# zx80_SD_12_smd_build002-001.net
KiCad netlist of a schematic drawn in EAGLE
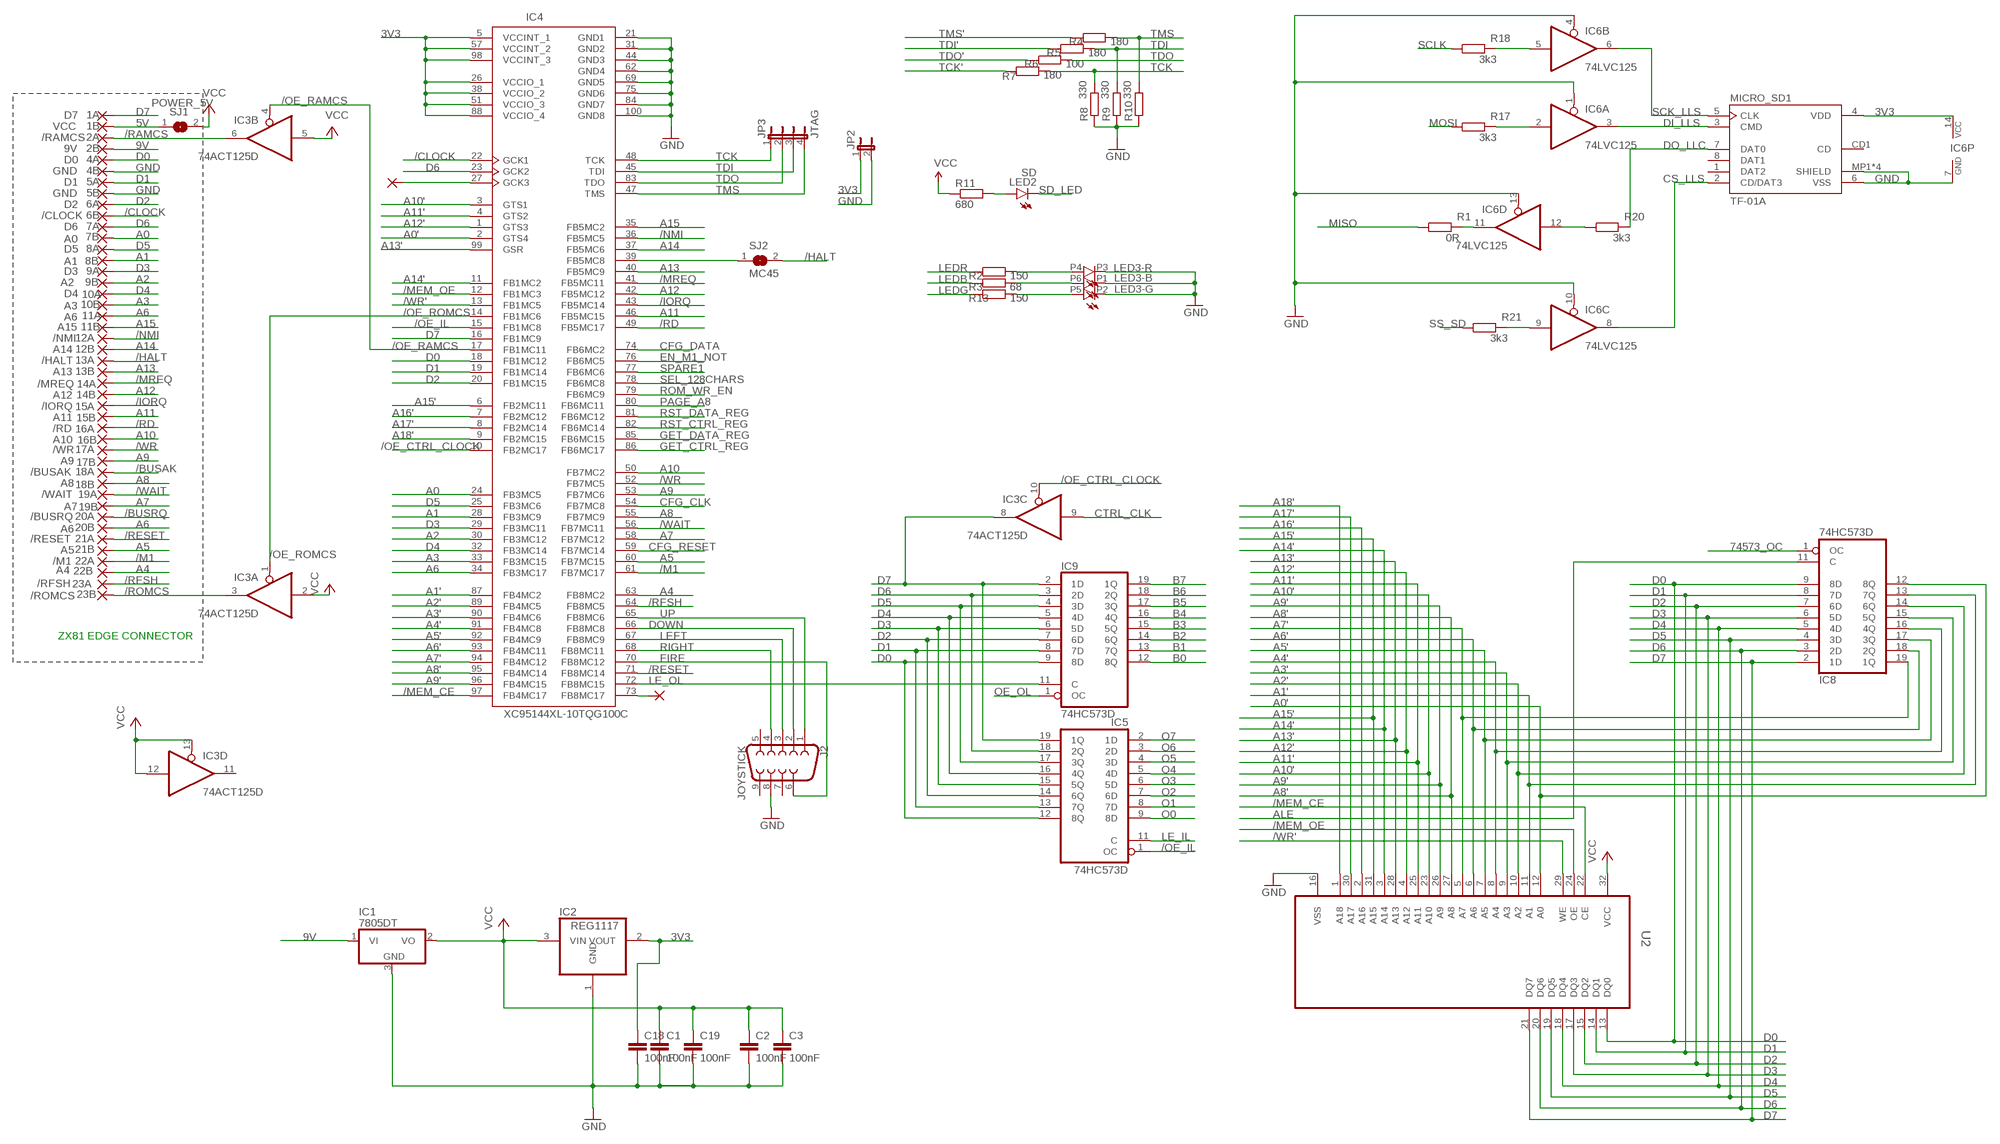
[diagram p0: schematic, sheet 1]
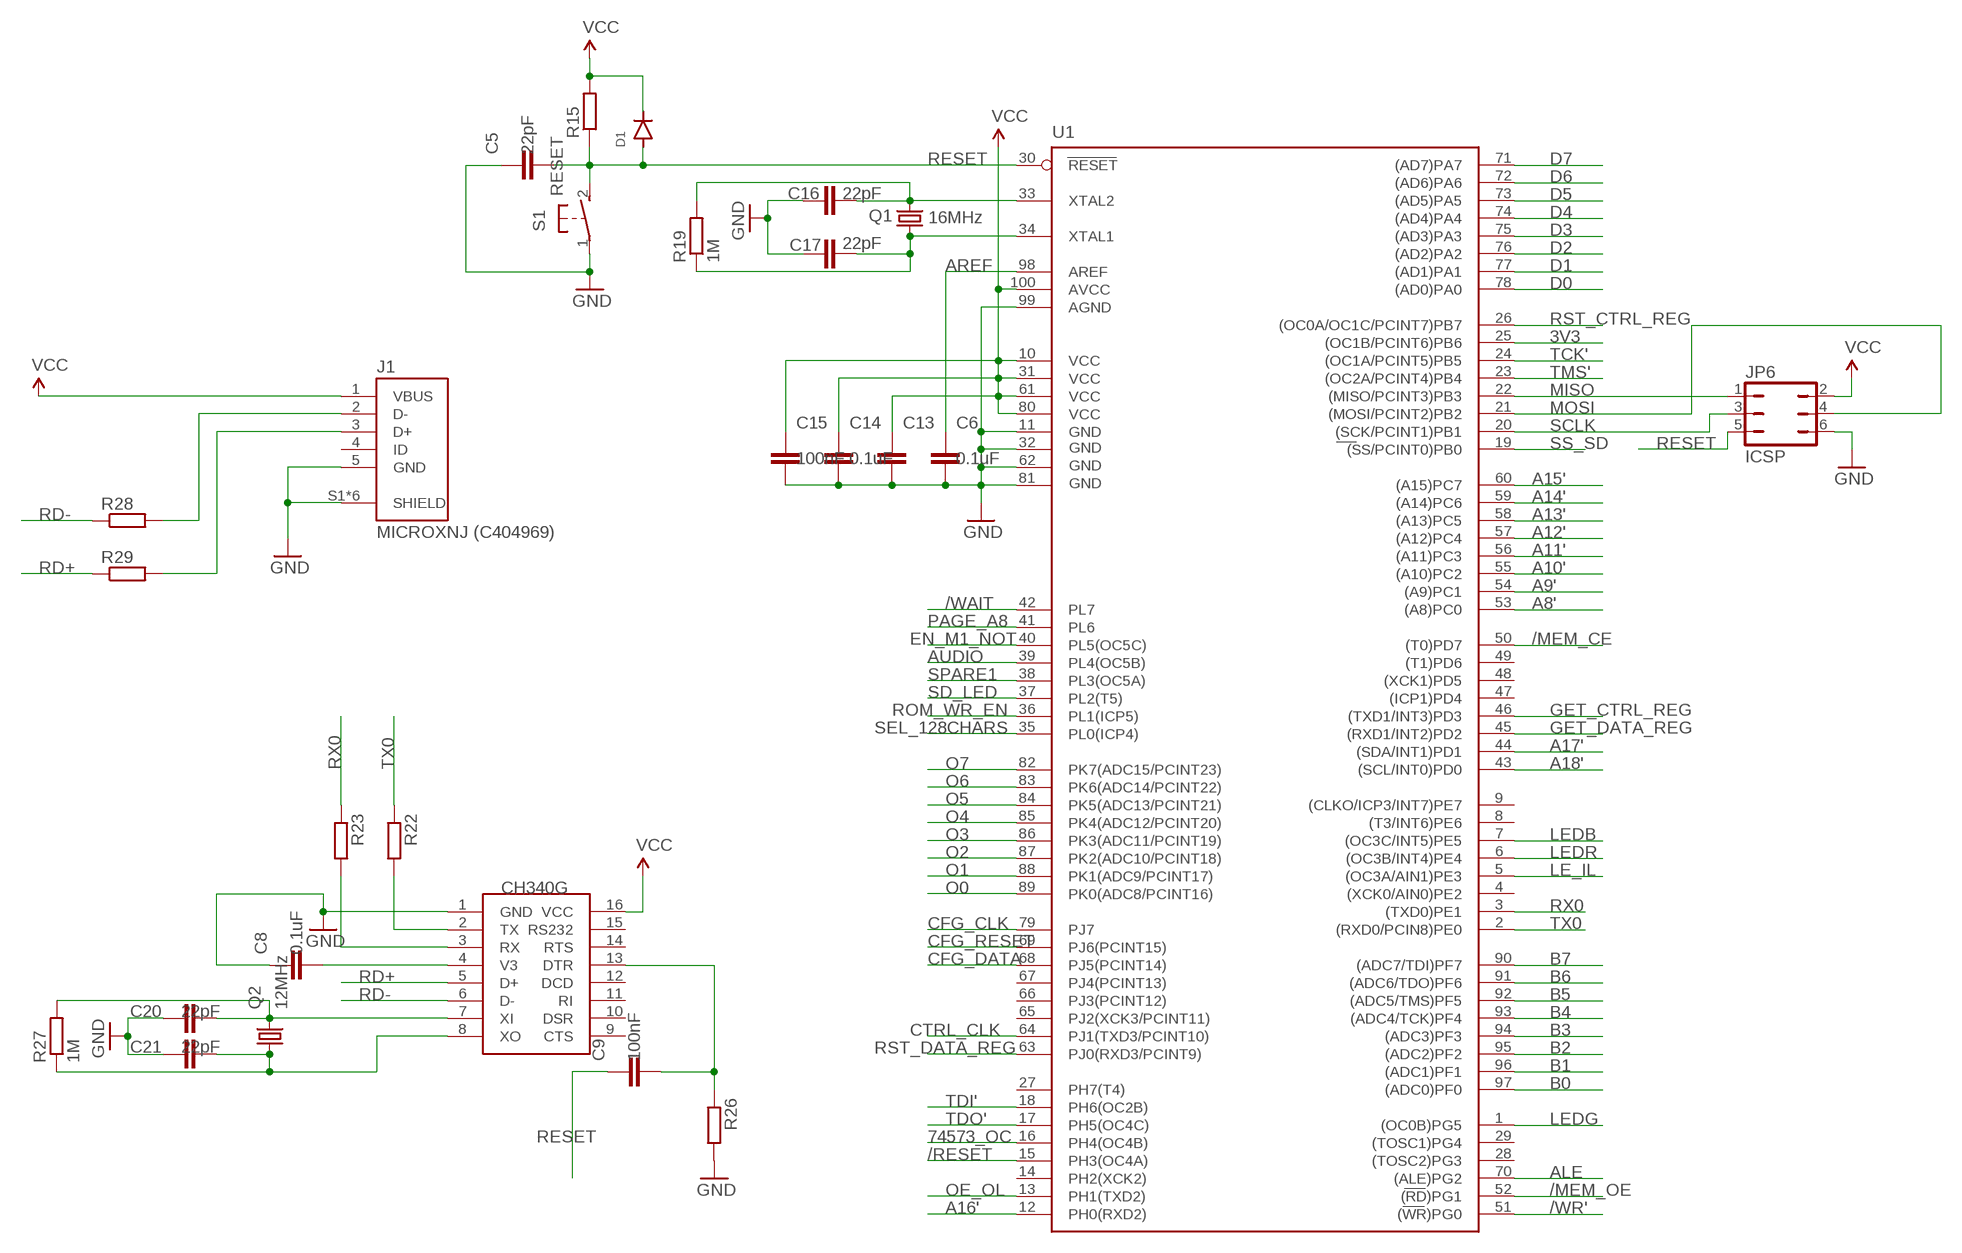
[diagram p1: schematic, sheet 2]

(export (version "E")
  (design (tool "Eeschema 10.0.6"))
  (components
    (comp (ref "C5")
      (value "22pF")
      (footprint "eagle-import:C0603")
      (libsource (lib "eagle-import") (part "C-EUC0603"))
    )
    (comp (ref "C6")
      (value "0.1uF")
      (footprint "eagle-import:C0603")
      (libsource (lib "eagle-import") (part "C-EUC0603"))
    )
    (comp (ref "C8")
      (value "0.1uF")
      (footprint "eagle-import:C0603")
      (libsource (lib "eagle-import") (part "C-EUC0603"))
    )
    (comp (ref "C9")
      (value "100nF")
      (footprint "eagle-import:C0603")
      (libsource (lib "eagle-import") (part "C-EUC0603"))
    )
    (comp (ref "C13")
      (value "0.1uF")
      (footprint "eagle-import:C0603")
      (libsource (lib "eagle-import") (part "C-EUC0603"))
    )
    (comp (ref "C14")
      (value "0.1uF")
      (footprint "eagle-import:C0603")
      (libsource (lib "eagle-import") (part "C-EUC0603"))
    )
    (comp (ref "C15")
      (value "100nF")
      (footprint "eagle-import:C0603")
      (libsource (lib "eagle-import") (part "C-EUC0603"))
    )
    (comp (ref "C16")
      (value "22pF")
      (footprint "eagle-import:C0603")
      (libsource (lib "eagle-import") (part "C-EUC0603"))
    )
    (comp (ref "C17")
      (value "22pF")
      (footprint "eagle-import:C0603")
      (libsource (lib "eagle-import") (part "C-EUC0603"))
    )
    (comp (ref "C20")
      (value "22pF")
      (footprint "eagle-import:C0603")
      (libsource (lib "eagle-import") (part "C-EUC0603"))
    )
    (comp (ref "C21")
      (value "22pF")
      (footprint "eagle-import:C0603")
      (libsource (lib "eagle-import") (part "C-EUC0603"))
    )
    (comp (ref "D1")
      (value "DIODE-SOD123")
      (footprint "eagle-import:SOD123")
      (libsource (lib "eagle-import") (part "DIODE-SOD123"))
    )
    (comp (ref "IC7")
      (value "CH340G")
      (footprint "eagle-import:SOIC16")
      (libsource (lib "eagle-import") (part "CH340G"))
    )
    (comp (ref "J1")
      (value "MICROXNJ (C404969)")
      (footprint "eagle-import:SHOUHAN_MICROXNJ")
      (fields (field (name "MF") "Shouhan") (field (name "MP") "MICROXNJ"))
      (libsource (lib "eagle-import") (part "MICROXNJ"))
    )
    (comp (ref "JP6")
      (value "ICSP")
      (footprint "eagle-import:JP3Q")
      (libsource (lib "eagle-import") (part "JP3Q"))
    )
    (comp (ref "Q1")
      (value "16MHz")
      (footprint "eagle-import:3.2X2.5_KX-7")
      (libsource (lib "eagle-import") (part "KX-7"))
    )
    (comp (ref "Q2")
      (value "12MHz")
      (footprint "eagle-import:3.2X2.5_KX-7")
      (libsource (lib "eagle-import") (part "KX-7"))
    )
    (comp (ref "R15")
      (value "R-EU_R0603")
      (footprint "eagle-import:R0603")
      (libsource (lib "eagle-import") (part "rcl_334_R-EU_R0603"))
    )
    (comp (ref "R19")
      (value "1M")
      (footprint "eagle-import:R0603")
      (libsource (lib "eagle-import") (part "rcl_334_R-EU_R0603"))
    )
    (comp (ref "R22")
      (value "1K")
      (footprint "eagle-import:R0603")
      (libsource (lib "eagle-import") (part "rcl_334_R-EU_R0603"))
    )
    (comp (ref "R23")
      (value "1K")
      (footprint "eagle-import:R0603")
      (libsource (lib "eagle-import") (part "rcl_334_R-EU_R0603"))
    )
    (comp (ref "R26")
      (value "1K")
      (footprint "eagle-import:R0603")
      (libsource (lib "eagle-import") (part "rcl_334_R-EU_R0603"))
    )
    (comp (ref "R27")
      (value "1M")
      (footprint "eagle-import:R0603")
      (libsource (lib "eagle-import") (part "rcl_334_R-EU_R0603"))
    )
    (comp (ref "R28")
      (value "22R")
      (footprint "eagle-import:R0603")
      (libsource (lib "eagle-import") (part "rcl_334_R-EU_R0603"))
    )
    (comp (ref "R29")
      (value "22R")
      (footprint "eagle-import:R0603")
      (libsource (lib "eagle-import") (part "rcl_334_R-EU_R0603"))
    )
    (comp (ref "S1")
      (value "RESET")
      (footprint "eagle-import:B3F-31XX")
      (fields (field (name "MPN") "B3F-3100"))
      (libsource (lib "eagle-import") (part "31-XX"))
    )
    (comp (ref "U1")
      (value "ATMEGA2560AU")
      (footprint "eagle-import:TQFP100")
      (libsource (lib "eagle-import") (part "ATMEGA2560AU"))
    )
    (comp (ref "1A")
      (value "D7")
      (footprint "eagle-import:EDGEPIN")
      (libsource (lib "eagle-import") (part "SMD2EDGEPIN"))
    )
    (comp (ref "1B")
      (value "VCC")
      (footprint "eagle-import:EDGEPIN")
      (libsource (lib "eagle-import") (part "SMD2EDGEPIN"))
    )
    (comp (ref "2A")
      (value "/RAMCS")
      (footprint "eagle-import:EDGEPIN")
      (libsource (lib "eagle-import") (part "SMD2EDGEPIN"))
    )
    (comp (ref "2B")
      (value "9V")
      (footprint "eagle-import:EDGEPIN")
      (libsource (lib "eagle-import") (part "SMD2EDGEPIN"))
    )
    (comp (ref "4A")
      (value "D0")
      (footprint "eagle-import:EDGEPIN")
      (libsource (lib "eagle-import") (part "SMD2EDGEPIN"))
    )
    (comp (ref "4B")
      (value "GND")
      (footprint "eagle-import:EDGEPIN")
      (libsource (lib "eagle-import") (part "SMD2EDGEPIN"))
    )
    (comp (ref "5A")
      (value "D1")
      (footprint "eagle-import:EDGEPIN")
      (libsource (lib "eagle-import") (part "SMD2EDGEPIN"))
    )
    (comp (ref "5B")
      (value "GND")
      (footprint "eagle-import:EDGEPIN")
      (libsource (lib "eagle-import") (part "SMD2EDGEPIN"))
    )
    (comp (ref "6A")
      (value "D2")
      (footprint "eagle-import:EDGEPIN")
      (libsource (lib "eagle-import") (part "SMD2EDGEPIN"))
    )
    (comp (ref "6B")
      (value "/CLOCK")
      (footprint "eagle-import:EDGEPIN")
      (libsource (lib "eagle-import") (part "SMD2EDGEPIN"))
    )
    (comp (ref "7A")
      (value "D6")
      (footprint "eagle-import:EDGEPIN")
      (libsource (lib "eagle-import") (part "SMD2EDGEPIN"))
    )
    (comp (ref "7B")
      (value "A0")
      (footprint "eagle-import:EDGEPIN")
      (libsource (lib "eagle-import") (part "SMD2EDGEPIN"))
    )
    (comp (ref "8A")
      (value "D5")
      (footprint "eagle-import:EDGEPIN")
      (libsource (lib "eagle-import") (part "SMD2EDGEPIN"))
    )
    (comp (ref "8B")
      (value "A1")
      (footprint "eagle-import:EDGEPIN")
      (libsource (lib "eagle-import") (part "SMD2EDGEPIN"))
    )
    (comp (ref "9A")
      (value "D3")
      (footprint "eagle-import:EDGEPIN")
      (libsource (lib "eagle-import") (part "SMD2EDGEPIN"))
    )
    (comp (ref "9B")
      (value "A2")
      (footprint "eagle-import:EDGEPIN")
      (libsource (lib "eagle-import") (part "SMD2EDGEPIN"))
    )
    (comp (ref "10A")
      (value "D4")
      (footprint "eagle-import:EDGEPIN")
      (libsource (lib "eagle-import") (part "SMD2EDGEPIN"))
    )
    (comp (ref "10B")
      (value "A3")
      (footprint "eagle-import:EDGEPIN")
      (libsource (lib "eagle-import") (part "SMD2EDGEPIN"))
    )
    (comp (ref "11A")
      (value "A6")
      (footprint "eagle-import:EDGEPIN")
      (libsource (lib "eagle-import") (part "SMD2EDGEPIN"))
    )
    (comp (ref "11B")
      (value "A15")
      (footprint "eagle-import:EDGEPIN")
      (libsource (lib "eagle-import") (part "SMD2EDGEPIN"))
    )
    (comp (ref "12A")
      (value "/NMI")
      (footprint "eagle-import:EDGEPIN")
      (libsource (lib "eagle-import") (part "SMD2EDGEPIN"))
    )
    (comp (ref "12B")
      (value "A14")
      (footprint "eagle-import:EDGEPIN")
      (libsource (lib "eagle-import") (part "SMD2EDGEPIN"))
    )
    (comp (ref "13A")
      (value "/HALT")
      (footprint "eagle-import:EDGEPIN")
      (libsource (lib "eagle-import") (part "SMD2EDGEPIN"))
    )
    (comp (ref "13B")
      (value "A13")
      (footprint "eagle-import:EDGEPIN")
      (libsource (lib "eagle-import") (part "SMD2EDGEPIN"))
    )
    (comp (ref "14A")
      (value "/MREQ")
      (footprint "eagle-import:EDGEPIN")
      (libsource (lib "eagle-import") (part "SMD2EDGEPIN"))
    )
    (comp (ref "14B")
      (value "A12")
      (footprint "eagle-import:EDGEPIN")
      (libsource (lib "eagle-import") (part "SMD2EDGEPIN"))
    )
    (comp (ref "15A")
      (value "/IORQ")
      (footprint "eagle-import:EDGEPIN")
      (libsource (lib "eagle-import") (part "SMD2EDGEPIN"))
    )
    (comp (ref "15B")
      (value "A11")
      (footprint "eagle-import:EDGEPIN")
      (libsource (lib "eagle-import") (part "SMD2EDGEPIN"))
    )
    (comp (ref "16A")
      (value "/RD")
      (footprint "eagle-import:EDGEPIN")
      (libsource (lib "eagle-import") (part "SMD2EDGEPIN"))
    )
    (comp (ref "16B")
      (value "A10")
      (footprint "eagle-import:EDGEPIN")
      (libsource (lib "eagle-import") (part "SMD2EDGEPIN"))
    )
    (comp (ref "17A")
      (value "/WR")
      (footprint "eagle-import:EDGEPIN")
      (libsource (lib "eagle-import") (part "SMD2EDGEPIN"))
    )
    (comp (ref "17B")
      (value "A9")
      (footprint "eagle-import:EDGEPIN")
      (libsource (lib "eagle-import") (part "SMD2EDGEPIN"))
    )
    (comp (ref "18A")
      (value "/BUSAK")
      (footprint "eagle-import:EDGEPIN")
      (libsource (lib "eagle-import") (part "SMD2EDGEPIN"))
    )
    (comp (ref "18B")
      (value "A8")
      (footprint "eagle-import:EDGEPIN")
      (libsource (lib "eagle-import") (part "SMD2EDGEPIN"))
    )
    (comp (ref "19A")
      (value "/WAIT")
      (footprint "eagle-import:EDGEPIN")
      (libsource (lib "eagle-import") (part "SMD2EDGEPIN"))
    )
    (comp (ref "19B")
      (value "A7")
      (footprint "eagle-import:EDGEPIN")
      (libsource (lib "eagle-import") (part "SMD2EDGEPIN"))
    )
    (comp (ref "20A")
      (value "/BUSRQ")
      (footprint "eagle-import:EDGEPIN")
      (libsource (lib "eagle-import") (part "SMD2EDGEPIN"))
    )
    (comp (ref "20B")
      (value "A6")
      (footprint "eagle-import:EDGEPIN")
      (libsource (lib "eagle-import") (part "SMD2EDGEPIN"))
    )
    (comp (ref "21A")
      (value "/RESET")
      (footprint "eagle-import:EDGEPIN")
      (libsource (lib "eagle-import") (part "SMD2EDGEPIN"))
    )
    (comp (ref "21B")
      (value "A5")
      (footprint "eagle-import:EDGEPIN")
      (libsource (lib "eagle-import") (part "SMD2EDGEPIN"))
    )
    (comp (ref "22A")
      (value "/M1")
      (footprint "eagle-import:EDGEPIN")
      (libsource (lib "eagle-import") (part "SMD2EDGEPIN"))
    )
    (comp (ref "22B")
      (value "A4")
      (footprint "eagle-import:EDGEPIN")
      (libsource (lib "eagle-import") (part "SMD2EDGEPIN"))
    )
    (comp (ref "23A")
      (value "/RFSH")
      (footprint "eagle-import:EDGEPIN")
      (libsource (lib "eagle-import") (part "SMD2EDGEPIN"))
    )
    (comp (ref "23B")
      (value "/ROMCS")
      (footprint "eagle-import:EDGEPIN")
      (libsource (lib "eagle-import") (part "SMD2EDGEPIN"))
    )
    (comp (ref "C1")
      (value "100nF")
      (footprint "eagle-import:C0603")
      (libsource (lib "eagle-import") (part "C-EUC0603"))
    )
    (comp (ref "C2")
      (value "100nF")
      (footprint "eagle-import:C0603")
      (libsource (lib "eagle-import") (part "C-EUC0603"))
    )
    (comp (ref "C3")
      (value "100nF")
      (footprint "eagle-import:C0603")
      (libsource (lib "eagle-import") (part "C-EUC0603"))
    )
    (comp (ref "C18")
      (value "100nF")
      (footprint "eagle-import:C0603")
      (libsource (lib "eagle-import") (part "C-EUC0603"))
    )
    (comp (ref "C19")
      (value "100nF")
      (footprint "eagle-import:C0603")
      (libsource (lib "eagle-import") (part "C-EUC0603"))
    )
    (comp (ref "IC1")
      (value "7805DT")
      (footprint "eagle-import:TO252")
      (libsource (lib "eagle-import") (part "78DT05"))
    )
    (comp (ref "IC2")
      (value "REG1117")
      (footprint "eagle-import:SOT223")
      (libsource (lib "eagle-import") (part "REG1117"))
    )
    (comp (ref "IC3")
      (value "74ACT125D")
      (footprint "eagle-import:SO14")
      (libsource (lib "eagle-import") (part "74125DACT"))
    )
    (comp (ref "IC4")
      (value "XC95144XL-10TQG100C")
      (footprint "eagle-import:TQFP100")
      (fields (field (name "MF") "Xilinx Inc."))
      (libsource (lib "eagle-import") (part "XC95144XL-10TQG100C"))
    )
    (comp (ref "IC5")
      (value "74HC573D")
      (footprint "eagle-import:SO20W")
      (libsource (lib "eagle-import") (part "74573DHC"))
    )
    (comp (ref "IC6")
      (value "74LVC125")
      (footprint "eagle-import:SO14")
      (libsource (lib "eagle-import") (part "74125DLS"))
    )
    (comp (ref "IC8")
      (value "74HC573D")
      (footprint "eagle-import:SO20W")
      (libsource (lib "eagle-import") (part "74573DHC"))
    )
    (comp (ref "IC9")
      (value "74HC573D")
      (footprint "eagle-import:SO20W")
      (libsource (lib "eagle-import") (part "74573DHC"))
    )
    (comp (ref "J2")
      (value "JOYSTICK")
      (footprint "eagle-import:DB9_MALE")
      (libsource (lib "eagle-import") (part "DB9MALE"))
    )
    (comp (ref "JP2")
      (value "JP1E")
      (footprint "eagle-import:JP1")
      (libsource (lib "eagle-import") (part "JP1E"))
    )
    (comp (ref "JP3")
      (value "JTAG")
      (footprint "eagle-import:JP4")
      (libsource (lib "eagle-import") (part "JP4E"))
    )
    (comp (ref "LED2")
      (value "SD")
      (footprint "eagle-import:CHIPLED_0603")
      (libsource (lib "eagle-import") (part "LEDCHIPLED_0603"))
    )
    (comp (ref "LED3")
      (value "RS-3535MWAR")
      (footprint "eagle-import:3535-PLCC6")
      (libsource (lib "eagle-import") (part "3535RGB3535RGB"))
    )
    (comp (ref "MICRO_SD1")
      (value "TF-01A")
      (footprint "eagle-import:TF-01A")
      (fields (field (name "MF") "HRO Electronics Co., Ltd."))
      (libsource (lib "eagle-import") (part "TF-01A"))
    )
    (comp (ref "PAD1")
      (value "1,6/0,8")
      (footprint "eagle-import:1,6_0,8")
      (libsource (lib "eagle-import") (part "1,6/0,8"))
    )
    (comp (ref "PAD6")
      (value "P73")
      (footprint "eagle-import:1,6_0,8")
      (libsource (lib "eagle-import") (part "1,6/0,8"))
    )
    (comp (ref "R1")
      (value "0R")
      (footprint "eagle-import:R0603")
      (libsource (lib "eagle-import") (part "R-EU_R0603"))
    )
    (comp (ref "R2")
      (value "150")
      (footprint "eagle-import:R0603")
      (libsource (lib "eagle-import") (part "rcl_334_R-EU_R0603"))
    )
    (comp (ref "R3")
      (value "68")
      (footprint "eagle-import:R0603")
      (libsource (lib "eagle-import") (part "rcl_334_R-EU_R0603"))
    )
    (comp (ref "R4")
      (value "180")
      (footprint "eagle-import:R0603")
      (libsource (lib "eagle-import") (part "rcl_334_R-EU_R0603"))
    )
    (comp (ref "R5")
      (value "180")
      (footprint "eagle-import:R0603")
      (libsource (lib "eagle-import") (part "rcl_334_R-EU_R0603"))
    )
    (comp (ref "R6")
      (value "100")
      (footprint "eagle-import:R0603")
      (libsource (lib "eagle-import") (part "rcl_334_R-EU_R0603"))
    )
    (comp (ref "R7")
      (value "180")
      (footprint "eagle-import:R0603")
      (libsource (lib "eagle-import") (part "rcl_334_R-EU_R0603"))
    )
    (comp (ref "R8")
      (value "330")
      (footprint "eagle-import:R0603")
      (libsource (lib "eagle-import") (part "rcl_334_R-EU_R0603"))
    )
    (comp (ref "R9")
      (value "330")
      (footprint "eagle-import:R0603")
      (libsource (lib "eagle-import") (part "rcl_334_R-EU_R0603"))
    )
    (comp (ref "R10")
      (value "330")
      (footprint "eagle-import:R0603")
      (libsource (lib "eagle-import") (part "rcl_334_R-EU_R0603"))
    )
    (comp (ref "R11")
      (value "680")
      (footprint "eagle-import:R0603")
      (libsource (lib "eagle-import") (part "R-EU_R0603"))
    )
    (comp (ref "R13")
      (value "150")
      (footprint "eagle-import:R0603")
      (libsource (lib "eagle-import") (part "rcl_334_R-EU_R0603"))
    )
    (comp (ref "R17")
      (value "3k3")
      (footprint "eagle-import:R0603")
      (libsource (lib "eagle-import") (part "R-EU_R0603"))
    )
    (comp (ref "R18")
      (value "3k3")
      (footprint "eagle-import:R0603")
      (libsource (lib "eagle-import") (part "R-EU_R0603"))
    )
    (comp (ref "R20")
      (value "3k3")
      (footprint "eagle-import:R0603")
      (libsource (lib "eagle-import") (part "R-EU_R0603"))
    )
    (comp (ref "R21")
      (value "3k3")
      (footprint "eagle-import:R0603")
      (libsource (lib "eagle-import") (part "R-EU_R0603"))
    )
    (comp (ref "SJ1")
      (value "POWER_5V")
      (footprint "eagle-import:SJ")
      (libsource (lib "eagle-import") (part "SJ"))
    )
    (comp (ref "SJ2")
      (value "MC45")
      (footprint "eagle-import:SJ")
      (libsource (lib "eagle-import") (part "SJ"))
    )
    (comp (ref "U2")
      (value "AS6C4008-55SINSOP5")
      (footprint "eagle-import:SOP32-5")
      (libsource (lib "eagle-import") (part "AS6C4008-55SINSOP5"))
    )
  )
  (nets
    (net (code "1") (name "3V3") (class "Default")
      (node (ref "C18") (pin "1") (pinfunction "1_1") (pintype "passive"))
      (node (ref "IC2") (pin "2") (pinfunction "VOUT_2") (pintype "output"))
      (node (ref "IC4") (pin "26") (pinfunction "VCCIO_1_26") (pintype "power_in"))
      (node (ref "IC4") (pin "38") (pinfunction "VCCIO_2_38") (pintype "power_in"))
      (node (ref "IC4") (pin "5") (pinfunction "VCCINT_1_5") (pintype "power_in"))
      (node (ref "IC4") (pin "51") (pinfunction "VCCIO_3_51") (pintype "power_in"))
      (node (ref "IC4") (pin "57") (pinfunction "VCCINT_2_57") (pintype "power_in"))
      (node (ref "IC4") (pin "88") (pinfunction "VCCIO_4_88") (pintype "power_in"))
      (node (ref "IC4") (pin "98") (pinfunction "VCCINT_3_98") (pintype "power_in"))
      (node (ref "IC6") (pin "14") (pinfunction "VCC_14") (pintype "power_in"))
      (node (ref "JP2") (pin "1") (pinfunction "1_1") (pintype "passive"))
      (node (ref "MICRO_SD1") (pin "4") (pinfunction "VDD_4") (pintype "power_in"))
      (node (ref "U1") (pin "25") (pinfunction "(OC1B/PCINT6)PB6_25") (pintype "bidirectional"))
    )
    (net (code "2") (name "5V") (class "Default")
      (node (ref "1B") (pin "1") (pinfunction "P_1") (pintype "passive"))
      (node (ref "SJ1") (pin "1") (pinfunction "1_1") (pintype "passive"))
    )
    (net (code "3") (name "9V") (class "Default")
      (node (ref "2B") (pin "1") (pinfunction "P_1") (pintype "passive"))
      (node (ref "IC1") (pin "1") (pinfunction "VI_1") (pintype "input"))
    )
    (net (code "4") (name "74573_OC") (class "Default")
      (node (ref "IC8") (pin "1") (pinfunction "OC_1") (pintype "input"))
      (node (ref "U1") (pin "16") (pinfunction "PH4(OC4B)_16") (pintype "bidirectional"))
    )
    (net (code "5") (name "A0") (class "Default")
      (node (ref "7B") (pin "1") (pinfunction "P_1") (pintype "passive"))
      (node (ref "IC4") (pin "24") (pinfunction "FB3MC5_24") (pintype "bidirectional"))
    )
    (net (code "6") (name "A0'") (class "Default")
      (node (ref "IC4") (pin "2") (pinfunction "GTS4_2") (pintype "bidirectional"))
      (node (ref "IC8") (pin "12") (pinfunction "8Q_12") (pintype "tri_state"))
      (node (ref "U2") (pin "12") (pinfunction "A0_12") (pintype "input"))
    )
    (net (code "7") (name "A1") (class "Default")
      (node (ref "8B") (pin "1") (pinfunction "P_1") (pintype "passive"))
      (node (ref "IC4") (pin "28") (pinfunction "FB3MC9_28") (pintype "bidirectional"))
    )
    (net (code "8") (name "A1'") (class "Default")
      (node (ref "IC4") (pin "87") (pinfunction "FB4MC2_87") (pintype "bidirectional"))
      (node (ref "IC8") (pin "13") (pinfunction "7Q_13") (pintype "tri_state"))
      (node (ref "U2") (pin "11") (pinfunction "A1_11") (pintype "input"))
    )
    (net (code "9") (name "A2") (class "Default")
      (node (ref "9B") (pin "1") (pinfunction "P_1") (pintype "passive"))
      (node (ref "IC4") (pin "30") (pinfunction "FB3MC12_30") (pintype "bidirectional"))
    )
    (net (code "10") (name "A2'") (class "Default")
      (node (ref "IC4") (pin "89") (pinfunction "FB4MC5_89") (pintype "bidirectional"))
      (node (ref "IC8") (pin "14") (pinfunction "6Q_14") (pintype "tri_state"))
      (node (ref "U2") (pin "10") (pinfunction "A2_10") (pintype "input"))
    )
    (net (code "11") (name "A3") (class "Default")
      (node (ref "10B") (pin "1") (pinfunction "P_1") (pintype "passive"))
      (node (ref "IC4") (pin "33") (pinfunction "FB3MC15_33") (pintype "bidirectional"))
    )
    (net (code "12") (name "A3'") (class "Default")
      (node (ref "IC4") (pin "90") (pinfunction "FB4MC6_90") (pintype "bidirectional"))
      (node (ref "IC8") (pin "15") (pinfunction "5Q_15") (pintype "tri_state"))
      (node (ref "U2") (pin "9") (pinfunction "A3_9") (pintype "input"))
    )
    (net (code "13") (name "A4") (class "Default")
      (node (ref "22B") (pin "1") (pinfunction "P_1") (pintype "passive"))
      (node (ref "IC4") (pin "63") (pinfunction "FB8MC2_63") (pintype "bidirectional"))
    )
    (net (code "14") (name "A4'") (class "Default")
      (node (ref "IC4") (pin "91") (pinfunction "FB4MC8_91") (pintype "bidirectional"))
      (node (ref "IC8") (pin "16") (pinfunction "4Q_16") (pintype "tri_state"))
      (node (ref "U2") (pin "8") (pinfunction "A4_8") (pintype "input"))
    )
    (net (code "15") (name "A5") (class "Default")
      (node (ref "21B") (pin "1") (pinfunction "P_1") (pintype "passive"))
      (node (ref "IC4") (pin "60") (pinfunction "FB7MC15_60") (pintype "bidirectional"))
    )
    (net (code "16") (name "A5'") (class "Default")
      (node (ref "IC4") (pin "92") (pinfunction "FB4MC9_92") (pintype "bidirectional"))
      (node (ref "IC8") (pin "17") (pinfunction "3Q_17") (pintype "tri_state"))
      (node (ref "U2") (pin "7") (pinfunction "A5_7") (pintype "input"))
    )
    (net (code "17") (name "A6") (class "Default")
      (node (ref "11A") (pin "1") (pinfunction "P_1") (pintype "passive"))
      (node (ref "20B") (pin "1") (pinfunction "P_1") (pintype "passive"))
      (node (ref "IC4") (pin "34") (pinfunction "FB3MC17_34") (pintype "bidirectional"))
    )
    (net (code "18") (name "A6'") (class "Default")
      (node (ref "IC4") (pin "93") (pinfunction "FB4MC11_93") (pintype "bidirectional"))
      (node (ref "IC8") (pin "18") (pinfunction "2Q_18") (pintype "tri_state"))
      (node (ref "U2") (pin "6") (pinfunction "A6_6") (pintype "input"))
    )
    (net (code "19") (name "A7") (class "Default")
      (node (ref "19B") (pin "1") (pinfunction "P_1") (pintype "passive"))
      (node (ref "IC4") (pin "58") (pinfunction "FB7MC12_58") (pintype "bidirectional"))
    )
    (net (code "20") (name "A7'") (class "Default")
      (node (ref "IC4") (pin "94") (pinfunction "FB4MC12_94") (pintype "bidirectional"))
      (node (ref "IC8") (pin "19") (pinfunction "1Q_19") (pintype "tri_state"))
      (node (ref "U2") (pin "5") (pinfunction "A7_5") (pintype "input"))
    )
    (net (code "21") (name "A8") (class "Default")
      (node (ref "18B") (pin "1") (pinfunction "P_1") (pintype "passive"))
      (node (ref "IC4") (pin "55") (pinfunction "FB7MC9_55") (pintype "bidirectional"))
    )
    (net (code "22") (name "A8'") (class "Default")
      (node (ref "IC4") (pin "95") (pinfunction "FB4MC14_95") (pintype "bidirectional"))
      (node (ref "U1") (pin "53") (pinfunction "(A8)PC0_53") (pintype "bidirectional"))
      (node (ref "U2") (pin "27") (pinfunction "A8_27") (pintype "input"))
    )
    (net (code "23") (name "A9") (class "Default")
      (node (ref "17B") (pin "1") (pinfunction "P_1") (pintype "passive"))
      (node (ref "IC4") (pin "53") (pinfunction "FB7MC6_53") (pintype "bidirectional"))
    )
    (net (code "24") (name "A9'") (class "Default")
      (node (ref "IC4") (pin "96") (pinfunction "FB4MC15_96") (pintype "bidirectional"))
      (node (ref "U1") (pin "54") (pinfunction "(A9)PC1_54") (pintype "bidirectional"))
      (node (ref "U2") (pin "26") (pinfunction "A9_26") (pintype "input"))
    )
    (net (code "25") (name "A10") (class "Default")
      (node (ref "16B") (pin "1") (pinfunction "P_1") (pintype "passive"))
      (node (ref "IC4") (pin "50") (pinfunction "FB7MC2_50") (pintype "bidirectional"))
    )
    (net (code "26") (name "A10'") (class "Default")
      (node (ref "IC4") (pin "3") (pinfunction "GTS1_3") (pintype "bidirectional"))
      (node (ref "U1") (pin "55") (pinfunction "(A10)PC2_55") (pintype "bidirectional"))
      (node (ref "U2") (pin "23") (pinfunction "A10_23") (pintype "input"))
    )
    (net (code "27") (name "A11") (class "Default")
      (node (ref "15B") (pin "1") (pinfunction "P_1") (pintype "passive"))
      (node (ref "IC4") (pin "46") (pinfunction "FB5MC15_46") (pintype "bidirectional"))
    )
    (net (code "28") (name "A11'") (class "Default")
      (node (ref "IC4") (pin "4") (pinfunction "GTS2_4") (pintype "bidirectional"))
      (node (ref "U1") (pin "56") (pinfunction "(A11)PC3_56") (pintype "bidirectional"))
      (node (ref "U2") (pin "25") (pinfunction "A11_25") (pintype "input"))
    )
    (net (code "29") (name "A12") (class "Default")
      (node (ref "14B") (pin "1") (pinfunction "P_1") (pintype "passive"))
      (node (ref "IC4") (pin "42") (pinfunction "FB5MC12_42") (pintype "bidirectional"))
    )
    (net (code "30") (name "A12'") (class "Default")
      (node (ref "IC4") (pin "1") (pinfunction "GTS3_1") (pintype "bidirectional"))
      (node (ref "U1") (pin "57") (pinfunction "(A12)PC4_57") (pintype "bidirectional"))
      (node (ref "U2") (pin "4") (pinfunction "A12_4") (pintype "input"))
    )
    (net (code "31") (name "A13") (class "Default")
      (node (ref "13B") (pin "1") (pinfunction "P_1") (pintype "passive"))
      (node (ref "IC4") (pin "40") (pinfunction "FB5MC9_40") (pintype "bidirectional"))
    )
    (net (code "32") (name "A13'") (class "Default")
      (node (ref "IC4") (pin "99") (pinfunction "GSR_99") (pintype "bidirectional"))
      (node (ref "U1") (pin "58") (pinfunction "(A13)PC5_58") (pintype "bidirectional"))
      (node (ref "U2") (pin "28") (pinfunction "A13_28") (pintype "input"))
    )
    (net (code "33") (name "A14") (class "Default")
      (node (ref "12B") (pin "1") (pinfunction "P_1") (pintype "passive"))
      (node (ref "IC4") (pin "37") (pinfunction "FB5MC6_37") (pintype "bidirectional"))
    )
    (net (code "34") (name "A14'") (class "Default")
      (node (ref "IC4") (pin "11") (pinfunction "FB1MC2_11") (pintype "bidirectional"))
      (node (ref "U1") (pin "59") (pinfunction "(A14)PC6_59") (pintype "bidirectional"))
      (node (ref "U2") (pin "3") (pinfunction "A14_3") (pintype "input"))
    )
    (net (code "35") (name "A15") (class "Default")
      (node (ref "11B") (pin "1") (pinfunction "P_1") (pintype "passive"))
      (node (ref "IC4") (pin "35") (pinfunction "FB5MC2_35") (pintype "bidirectional"))
    )
    (net (code "36") (name "A15'") (class "Default")
      (node (ref "IC4") (pin "6") (pinfunction "FB2MC11_6") (pintype "bidirectional"))
      (node (ref "U1") (pin "60") (pinfunction "(A15)PC7_60") (pintype "bidirectional"))
      (node (ref "U2") (pin "31") (pinfunction "A15_31") (pintype "input"))
    )
    (net (code "37") (name "A16'") (class "Default")
      (node (ref "IC4") (pin "7") (pinfunction "FB2MC12_7") (pintype "bidirectional"))
      (node (ref "U1") (pin "12") (pinfunction "PH0(RXD2)_12") (pintype "bidirectional"))
      (node (ref "U2") (pin "2") (pinfunction "A16_2") (pintype "input"))
    )
    (net (code "38") (name "A17'") (class "Default")
      (node (ref "IC4") (pin "8") (pinfunction "FB2MC14_8") (pintype "bidirectional"))
      (node (ref "U1") (pin "44") (pinfunction "(SDA/INT1)PD1_44") (pintype "bidirectional"))
      (node (ref "U2") (pin "30") (pinfunction "A17_30") (pintype "input"))
    )
    (net (code "39") (name "A18'") (class "Default")
      (node (ref "IC4") (pin "9") (pinfunction "FB2MC15_9") (pintype "bidirectional"))
      (node (ref "U1") (pin "43") (pinfunction "(SCL/INT0)PD0_43") (pintype "bidirectional"))
      (node (ref "U2") (pin "1") (pinfunction "A18_1") (pintype "input"))
    )
    (net (code "40") (name "ALE") (class "Default")
      (node (ref "IC8") (pin "11") (pinfunction "C_11") (pintype "input"))
      (node (ref "U1") (pin "70") (pinfunction "(ALE)PG2_70") (pintype "bidirectional"))
    )
    (net (code "41") (name "AREF") (class "Default")
      (node (ref "C6") (pin "1") (pinfunction "1_1") (pintype "passive"))
      (node (ref "U1") (pin "98") (pinfunction "AREF_98") (pintype "bidirectional"))
    )
    (net (code "42") (name "AUDIO") (class "Default")
      (node (ref "U1") (pin "39") (pinfunction "PL4(OC5B)_39") (pintype "bidirectional"))
    )
    (net (code "43") (name "B0") (class "Default")
      (node (ref "IC9") (pin "12") (pinfunction "8Q_12") (pintype "tri_state"))
      (node (ref "U1") (pin "97") (pinfunction "(ADC0)PF0_97") (pintype "bidirectional"))
    )
    (net (code "44") (name "B1") (class "Default")
      (node (ref "IC9") (pin "13") (pinfunction "7Q_13") (pintype "tri_state"))
      (node (ref "U1") (pin "96") (pinfunction "(ADC1)PF1_96") (pintype "bidirectional"))
    )
    (net (code "45") (name "B2") (class "Default")
      (node (ref "IC9") (pin "14") (pinfunction "6Q_14") (pintype "tri_state"))
      (node (ref "U1") (pin "95") (pinfunction "(ADC2)PF2_95") (pintype "bidirectional"))
    )
    (net (code "46") (name "B3") (class "Default")
      (node (ref "IC9") (pin "15") (pinfunction "5Q_15") (pintype "tri_state"))
      (node (ref "U1") (pin "94") (pinfunction "(ADC3)PF3_94") (pintype "bidirectional"))
    )
    (net (code "47") (name "B4") (class "Default")
      (node (ref "IC9") (pin "16") (pinfunction "4Q_16") (pintype "tri_state"))
      (node (ref "U1") (pin "93") (pinfunction "(ADC4/TCK)PF4_93") (pintype "bidirectional"))
    )
    (net (code "48") (name "B5") (class "Default")
      (node (ref "IC9") (pin "17") (pinfunction "3Q_17") (pintype "tri_state"))
      (node (ref "U1") (pin "92") (pinfunction "(ADC5/TMS)PF5_92") (pintype "bidirectional"))
    )
    (net (code "49") (name "B6") (class "Default")
      (node (ref "IC9") (pin "18") (pinfunction "2Q_18") (pintype "tri_state"))
      (node (ref "U1") (pin "91") (pinfunction "(ADC6/TDO)PF6_91") (pintype "bidirectional"))
    )
    (net (code "50") (name "B7") (class "Default")
      (node (ref "IC9") (pin "19") (pinfunction "1Q_19") (pintype "tri_state"))
      (node (ref "U1") (pin "90") (pinfunction "(ADC7/TDI)PF7_90") (pintype "bidirectional"))
    )
    (net (code "51") (name "CFG_CLK") (class "Default")
      (node (ref "IC4") (pin "54") (pinfunction "FB7MC8_54") (pintype "bidirectional"))
      (node (ref "U1") (pin "79") (pinfunction "PJ7_79") (pintype "bidirectional"))
    )
    (net (code "52") (name "CFG_DATA") (class "Default")
      (node (ref "IC4") (pin "74") (pinfunction "FB6MC2_74") (pintype "bidirectional"))
      (node (ref "U1") (pin "68") (pinfunction "PJ5(PCINT14)_68") (pintype "bidirectional"))
    )
    (net (code "53") (name "CFG_RESET") (class "Default")
      (node (ref "IC4") (pin "59") (pinfunction "FB7MC14_59") (pintype "bidirectional"))
      (node (ref "U1") (pin "69") (pinfunction "PJ6(PCINT15)_69") (pintype "bidirectional"))
    )
    (net (code "54") (name "CS_LLS") (class "Default")
      (node (ref "IC6") (pin "8") (pinfunction "O_8") (pintype "tri_state"))
      (node (ref "MICRO_SD1") (pin "2") (pinfunction "CD/DAT3_2") (pintype "bidirectional"))
    )
    (net (code "55") (name "CTRL_CLK") (class "Default")
      (node (ref "IC3") (pin "9") (pinfunction "I_9") (pintype "input"))
      (node (ref "U1") (pin "64") (pinfunction "PJ1(TXD3/PCINT10)_64") (pintype "bidirectional"))
    )
    (net (code "56") (name "D0") (class "Default")
      (node (ref "4A") (pin "1") (pinfunction "P_1") (pintype "passive"))
      (node (ref "IC4") (pin "18") (pinfunction "FB1MC12_18") (pintype "bidirectional"))
      (node (ref "IC5") (pin "12") (pinfunction "8Q_12") (pintype "tri_state"))
      (node (ref "IC8") (pin "9") (pinfunction "8D_9") (pintype "input"))
      (node (ref "IC9") (pin "9") (pinfunction "8D_9") (pintype "input"))
      (node (ref "U1") (pin "78") (pinfunction "(AD0)PA0_78") (pintype "bidirectional"))
      (node (ref "U2") (pin "13") (pinfunction "DQ0_13") (pintype "output"))
    )
    (net (code "57") (name "D1") (class "Default")
      (node (ref "5A") (pin "1") (pinfunction "P_1") (pintype "passive"))
      (node (ref "IC4") (pin "19") (pinfunction "FB1MC14_19") (pintype "bidirectional"))
      (node (ref "IC5") (pin "13") (pinfunction "7Q_13") (pintype "tri_state"))
      (node (ref "IC8") (pin "8") (pinfunction "7D_8") (pintype "input"))
      (node (ref "IC9") (pin "8") (pinfunction "7D_8") (pintype "input"))
      (node (ref "U1") (pin "77") (pinfunction "(AD1)PA1_77") (pintype "bidirectional"))
      (node (ref "U2") (pin "14") (pinfunction "DQ1_14") (pintype "output"))
    )
    (net (code "58") (name "D2") (class "Default")
      (node (ref "6A") (pin "1") (pinfunction "P_1") (pintype "passive"))
      (node (ref "IC4") (pin "20") (pinfunction "FB1MC15_20") (pintype "bidirectional"))
      (node (ref "IC5") (pin "14") (pinfunction "6Q_14") (pintype "tri_state"))
      (node (ref "IC8") (pin "7") (pinfunction "6D_7") (pintype "input"))
      (node (ref "IC9") (pin "7") (pinfunction "6D_7") (pintype "input"))
      (node (ref "U1") (pin "76") (pinfunction "(AD2)PA2_76") (pintype "bidirectional"))
      (node (ref "U2") (pin "15") (pinfunction "DQ2_15") (pintype "output"))
    )
    (net (code "59") (name "D3") (class "Default")
      (node (ref "9A") (pin "1") (pinfunction "P_1") (pintype "passive"))
      (node (ref "IC4") (pin "29") (pinfunction "FB3MC11_29") (pintype "bidirectional"))
      (node (ref "IC5") (pin "15") (pinfunction "5Q_15") (pintype "tri_state"))
      (node (ref "IC8") (pin "6") (pinfunction "5D_6") (pintype "input"))
      (node (ref "IC9") (pin "6") (pinfunction "5D_6") (pintype "input"))
      (node (ref "U1") (pin "75") (pinfunction "(AD3)PA3_75") (pintype "bidirectional"))
      (node (ref "U2") (pin "17") (pinfunction "DQ3_17") (pintype "output"))
    )
    (net (code "60") (name "D4") (class "Default")
      (node (ref "10A") (pin "1") (pinfunction "P_1") (pintype "passive"))
      (node (ref "IC4") (pin "32") (pinfunction "FB3MC14_32") (pintype "bidirectional"))
      (node (ref "IC5") (pin "16") (pinfunction "4Q_16") (pintype "tri_state"))
      (node (ref "IC8") (pin "5") (pinfunction "4D_5") (pintype "input"))
      (node (ref "IC9") (pin "5") (pinfunction "4D_5") (pintype "input"))
      (node (ref "U1") (pin "74") (pinfunction "(AD4)PA4_74") (pintype "bidirectional"))
      (node (ref "U2") (pin "18") (pinfunction "DQ4_18") (pintype "output"))
    )
    (net (code "61") (name "D5") (class "Default")
      (node (ref "8A") (pin "1") (pinfunction "P_1") (pintype "passive"))
      (node (ref "IC4") (pin "25") (pinfunction "FB3MC6_25") (pintype "bidirectional"))
      (node (ref "IC5") (pin "17") (pinfunction "3Q_17") (pintype "tri_state"))
      (node (ref "IC8") (pin "4") (pinfunction "3D_4") (pintype "input"))
      (node (ref "IC9") (pin "4") (pinfunction "3D_4") (pintype "input"))
      (node (ref "U1") (pin "73") (pinfunction "(AD5)PA5_73") (pintype "bidirectional"))
      (node (ref "U2") (pin "19") (pinfunction "DQ5_19") (pintype "output"))
    )
    (net (code "62") (name "D6") (class "Default")
      (node (ref "7A") (pin "1") (pinfunction "P_1") (pintype "passive"))
      (node (ref "IC4") (pin "23") (pinfunction "GCK2_23") (pintype "bidirectional"))
      (node (ref "IC5") (pin "18") (pinfunction "2Q_18") (pintype "tri_state"))
      (node (ref "IC8") (pin "3") (pinfunction "2D_3") (pintype "input"))
      (node (ref "IC9") (pin "3") (pinfunction "2D_3") (pintype "input"))
      (node (ref "U1") (pin "72") (pinfunction "(AD6)PA6_72") (pintype "bidirectional"))
      (node (ref "U2") (pin "20") (pinfunction "DQ6_20") (pintype "output"))
    )
    (net (code "63") (name "D7") (class "Default")
      (node (ref "1A") (pin "1") (pinfunction "P_1") (pintype "passive"))
      (node (ref "IC3") (pin "8") (pinfunction "O_8") (pintype "tri_state"))
      (node (ref "IC4") (pin "16") (pinfunction "FB1MC9_16") (pintype "bidirectional"))
      (node (ref "IC5") (pin "19") (pinfunction "1Q_19") (pintype "tri_state"))
      (node (ref "IC8") (pin "2") (pinfunction "1D_2") (pintype "input"))
      (node (ref "IC9") (pin "2") (pinfunction "1D_2") (pintype "input"))
      (node (ref "U1") (pin "71") (pinfunction "(AD7)PA7_71") (pintype "bidirectional"))
      (node (ref "U2") (pin "21") (pinfunction "DQ7_21") (pintype "output"))
    )
    (net (code "64") (name "DI_LLS") (class "Default")
      (node (ref "IC6") (pin "3") (pinfunction "O_3") (pintype "tri_state"))
      (node (ref "MICRO_SD1") (pin "3") (pinfunction "CMD_3") (pintype "bidirectional"))
    )
    (net (code "65") (name "DOWN") (class "Default")
      (node (ref "IC4") (pin "66") (pinfunction "FB8MC8_66") (pintype "bidirectional"))
      (node (ref "J2") (pin "2") (pinfunction "2_2") (pintype "passive"))
    )
    (net (code "66") (name "DO_LLC") (class "Default")
      (node (ref "IC6") (pin "12") (pinfunction "I_12") (pintype "input"))
      (node (ref "R20") (pin "1") (pinfunction "1_1") (pintype "passive"))
    )
    (net (code "67") (name "EN_M1_NOT") (class "Default")
      (node (ref "IC4") (pin "76") (pinfunction "FB6MC5_76") (pintype "bidirectional"))
      (node (ref "U1") (pin "40") (pinfunction "PL5(OC5C)_40") (pintype "bidirectional"))
    )
    (net (code "68") (name "FIRE") (class "Default")
      (node (ref "IC4") (pin "70") (pinfunction "FB8MC12_70") (pintype "bidirectional"))
      (node (ref "J2") (pin "6") (pinfunction "6_6") (pintype "passive"))
    )
    (net (code "69") (name "GET_CTRL_REG") (class "Default")
      (node (ref "IC4") (pin "86") (pinfunction "FB6MC17_86") (pintype "bidirectional"))
      (node (ref "U1") (pin "46") (pinfunction "(TXD1/INT3)PD3_46") (pintype "bidirectional"))
    )
    (net (code "70") (name "GET_DATA_REG") (class "Default")
      (node (ref "IC4") (pin "85") (pinfunction "FB6MC15_85") (pintype "bidirectional"))
      (node (ref "U1") (pin "45") (pinfunction "(RXD1/INT2)PD2_45") (pintype "bidirectional"))
    )
    (net (code "71") (name "GND") (class "Default")
      (node (ref "4B") (pin "1") (pinfunction "P_1") (pintype "passive"))
      (node (ref "5B") (pin "1") (pinfunction "P_1") (pintype "passive"))
      (node (ref "C1") (pin "2") (pinfunction "2_2") (pintype "passive"))
      (node (ref "C13") (pin "2") (pinfunction "2_2") (pintype "passive"))
      (node (ref "C14") (pin "2") (pinfunction "2_2") (pintype "passive"))
      (node (ref "C15") (pin "2") (pinfunction "2_2") (pintype "passive"))
      (node (ref "C16") (pin "1") (pinfunction "1_1") (pintype "passive"))
      (node (ref "C17") (pin "1") (pinfunction "1_1") (pintype "passive"))
      (node (ref "C18") (pin "2") (pinfunction "2_2") (pintype "passive"))
      (node (ref "C19") (pin "2") (pinfunction "2_2") (pintype "passive"))
      (node (ref "C2") (pin "2") (pinfunction "2_2") (pintype "passive"))
      (node (ref "C20") (pin "1") (pinfunction "1_1") (pintype "passive"))
      (node (ref "C21") (pin "1") (pinfunction "1_1") (pintype "passive"))
      (node (ref "C3") (pin "2") (pinfunction "2_2") (pintype "passive"))
      (node (ref "C5") (pin "1") (pinfunction "1_1") (pintype "passive"))
      (node (ref "C6") (pin "2") (pinfunction "2_2") (pintype "passive"))
      (node (ref "C8") (pin "1") (pinfunction "1_1") (pintype "passive"))
      (node (ref "IC1") (pin "3") (pinfunction "GND_3") (pintype "passive"))
      (node (ref "IC2") (pin "1") (pinfunction "GND_1") (pintype "power_in"))
      (node (ref "IC4") (pin "100") (pinfunction "GND8_100") (pintype "power_in"))
      (node (ref "IC4") (pin "21") (pinfunction "GND1_21") (pintype "power_in"))
      (node (ref "IC4") (pin "31") (pinfunction "GND2_31") (pintype "power_in"))
      (node (ref "IC4") (pin "44") (pinfunction "GND3_44") (pintype "power_in"))
      (node (ref "IC4") (pin "62") (pinfunction "GND4_62") (pintype "power_in"))
      (node (ref "IC4") (pin "69") (pinfunction "GND5_69") (pintype "power_in"))
      (node (ref "IC4") (pin "75") (pinfunction "GND6_75") (pintype "power_in"))
      (node (ref "IC4") (pin "84") (pinfunction "GND7_84") (pintype "power_in"))
      (node (ref "IC6") (pin "1") (pinfunction "OE_1") (pintype "input"))
      (node (ref "IC6") (pin "10") (pinfunction "OE_10") (pintype "input"))
      (node (ref "IC6") (pin "13") (pinfunction "OE_13") (pintype "input"))
      (node (ref "IC6") (pin "4") (pinfunction "OE_4") (pintype "input"))
      (node (ref "IC6") (pin "7") (pinfunction "GND_7") (pintype "power_in"))
      (node (ref "IC7") (pin "1") (pinfunction "GND_1") (pintype "bidirectional"))
      (node (ref "J1") (pin "5") (pinfunction "GND_5") (pintype "power_in"))
      (node (ref "J1") (pin "S1") (pinfunction "SHIELD_S1") (pintype "passive"))
      (node (ref "J1") (pin "S2") (pinfunction "SHIELD_S2") (pintype "passive"))
      (node (ref "J1") (pin "S3") (pinfunction "SHIELD_S3") (pintype "passive"))
      (node (ref "J1") (pin "S4") (pinfunction "SHIELD_S4") (pintype "passive"))
      (node (ref "J1") (pin "S5") (pinfunction "SHIELD_S5") (pintype "passive"))
      (node (ref "J1") (pin "S6") (pinfunction "SHIELD_S6") (pintype "passive"))
      (node (ref "J2") (pin "8") (pinfunction "8_8") (pintype "passive"))
      (node (ref "JP2") (pin "2") (pinfunction "2_2") (pintype "passive"))
      (node (ref "JP6") (pin "6") (pinfunction "6_6") (pintype "passive"))
      (node (ref "LED3") (pin "P1") (pinfunction "C_P1") (pintype "passive"))
      (node (ref "LED3") (pin "P2") (pinfunction "C_P2") (pintype "passive"))
      (node (ref "LED3") (pin "P3") (pinfunction "C_P3") (pintype "passive"))
      (node (ref "MICRO_SD1") (pin "6") (pinfunction "VSS_6") (pintype "power_in"))
      (node (ref "MICRO_SD1") (pin "MP1") (pinfunction "SHIELD_MP1") (pintype "power_in"))
      (node (ref "MICRO_SD1") (pin "MP2") (pinfunction "SHIELD_MP2") (pintype "power_in"))
      (node (ref "MICRO_SD1") (pin "MP3") (pinfunction "SHIELD_MP3") (pintype "power_in"))
      (node (ref "MICRO_SD1") (pin "MP4") (pinfunction "SHIELD_MP4") (pintype "power_in"))
      (node (ref "R10") (pin "1") (pinfunction "1_1") (pintype "passive"))
      (node (ref "R26") (pin "2") (pinfunction "2_2") (pintype "passive"))
      (node (ref "R8") (pin "1") (pinfunction "1_1") (pintype "passive"))
      (node (ref "R9") (pin "1") (pinfunction "1_1") (pintype "passive"))
      (node (ref "S1") (pin "1") (pinfunction "P_1") (pintype "passive"))
      (node (ref "U1") (pin "11") (pinfunction "GND_11") (pintype "power_in"))
      (node (ref "U1") (pin "32") (pinfunction "GND1_32") (pintype "power_in"))
      (node (ref "U1") (pin "62") (pinfunction "GND2_62") (pintype "power_in"))
      (node (ref "U1") (pin "81") (pinfunction "GND3_81") (pintype "power_in"))
      (node (ref "U1") (pin "99") (pinfunction "AGND_99") (pintype "power_in"))
      (node (ref "U2") (pin "16") (pinfunction "VSS_16") (pintype "output"))
    )
    (net (code "72") (name "LEDB") (class "Default")
      (node (ref "R3") (pin "1") (pinfunction "1_1") (pintype "passive"))
      (node (ref "U1") (pin "7") (pinfunction "(OC3C/INT5)PE5_7") (pintype "bidirectional"))
    )
    (net (code "73") (name "LEDG") (class "Default")
      (node (ref "R13") (pin "1") (pinfunction "1_1") (pintype "passive"))
      (node (ref "U1") (pin "1") (pinfunction "(OC0B)PG5_1") (pintype "bidirectional"))
    )
    (net (code "74") (name "LEDR") (class "Default")
      (node (ref "R2") (pin "1") (pinfunction "1_1") (pintype "passive"))
      (node (ref "U1") (pin "6") (pinfunction "(OC3B/INT4)PE4_6") (pintype "bidirectional"))
    )
    (net (code "75") (name "LEFT") (class "Default")
      (node (ref "IC4") (pin "67") (pinfunction "FB8MC9_67") (pintype "bidirectional"))
      (node (ref "J2") (pin "3") (pinfunction "3_3") (pintype "passive"))
    )
    (net (code "76") (name "LE_IL") (class "Default")
      (node (ref "IC5") (pin "11") (pinfunction "C_11") (pintype "input"))
      (node (ref "U1") (pin "5") (pinfunction "(OC3A/AIN1)PE3_5") (pintype "bidirectional"))
    )
    (net (code "77") (name "LE_OL") (class "Default")
      (node (ref "IC4") (pin "72") (pinfunction "FB8MC15_72") (pintype "bidirectional"))
      (node (ref "IC9") (pin "11") (pinfunction "C_11") (pintype "input"))
    )
    (net (code "78") (name "MISO") (class "Default")
      (node (ref "JP6") (pin "1") (pinfunction "1_1") (pintype "passive"))
      (node (ref "R1") (pin "1") (pinfunction "1_1") (pintype "passive"))
      (node (ref "U1") (pin "22") (pinfunction "(MISO/PCINT3)PB3_22") (pintype "bidirectional"))
    )
    (net (code "79") (name "MOSI") (class "Default")
      (node (ref "JP6") (pin "4") (pinfunction "4_4") (pintype "passive"))
      (node (ref "R17") (pin "1") (pinfunction "1_1") (pintype "passive"))
      (node (ref "U1") (pin "21") (pinfunction "(MOSI/PCINT2)PB2_21") (pintype "bidirectional"))
    )
    (net (code "80") (name "Net-(IC4-FB5MC8)") (class "Default")
      (node (ref "IC4") (pin "39") (pinfunction "FB5MC8_39") (pintype "bidirectional"))
      (node (ref "SJ2") (pin "1") (pinfunction "1_1") (pintype "passive"))
    )
    (net (code "81") (name "Net-(IC4-FB8MC17)") (class "Default")
      (node (ref "IC4") (pin "73") (pinfunction "FB8MC17_73") (pintype "bidirectional"))
      (node (ref "PAD6") (pin "1") (pinfunction "P_1") (pintype "passive"))
    )
    (net (code "82") (name "Net-(IC4-GCK3)") (class "Default")
      (node (ref "IC4") (pin "27") (pinfunction "GCK3_27") (pintype "bidirectional"))
      (node (ref "PAD1") (pin "1") (pinfunction "P_1") (pintype "passive"))
    )
    (net (code "83") (name "Net-(IC6A-I)") (class "Default")
      (node (ref "IC6") (pin "2") (pinfunction "I_2") (pintype "input"))
      (node (ref "R17") (pin "2") (pinfunction "2_2") (pintype "passive"))
    )
    (net (code "84") (name "Net-(IC6B-I)") (class "Default")
      (node (ref "IC6") (pin "5") (pinfunction "I_5") (pintype "input"))
      (node (ref "R18") (pin "2") (pinfunction "2_2") (pintype "passive"))
    )
    (net (code "85") (name "Net-(IC6C-I)") (class "Default")
      (node (ref "IC6") (pin "9") (pinfunction "I_9") (pintype "input"))
      (node (ref "R21") (pin "2") (pinfunction "2_2") (pintype "passive"))
    )
    (net (code "86") (name "Net-(IC6D-O)") (class "Default")
      (node (ref "IC6") (pin "11") (pinfunction "O_11") (pintype "tri_state"))
      (node (ref "R1") (pin "2") (pinfunction "2_2") (pintype "passive"))
    )
    (net (code "87") (name "Net-(IC7-DTR)") (class "Default")
      (node (ref "C9") (pin "2") (pinfunction "2_2") (pintype "passive"))
      (node (ref "IC7") (pin "13") (pinfunction "DTR_13") (pintype "bidirectional"))
      (node (ref "R26") (pin "1") (pinfunction "1_1") (pintype "passive"))
    )
    (net (code "88") (name "Net-(IC7-RX)") (class "Default")
      (node (ref "IC7") (pin "3") (pinfunction "RX_3") (pintype "bidirectional"))
      (node (ref "R23") (pin "2") (pinfunction "2_2") (pintype "passive"))
    )
    (net (code "89") (name "Net-(IC7-TX)") (class "Default")
      (node (ref "IC7") (pin "2") (pinfunction "TX_2") (pintype "bidirectional"))
      (node (ref "R22") (pin "2") (pinfunction "2_2") (pintype "passive"))
    )
    (net (code "90") (name "Net-(IC7-V3)") (class "Default")
      (node (ref "C8") (pin "2") (pinfunction "2_2") (pintype "passive"))
      (node (ref "IC7") (pin "4") (pinfunction "V3_4") (pintype "bidirectional"))
    )
    (net (code "91") (name "Net-(IC7-XI)") (class "Default")
      (node (ref "C20") (pin "2") (pinfunction "2_2") (pintype "passive"))
      (node (ref "IC7") (pin "7") (pinfunction "XI_7") (pintype "bidirectional"))
      (node (ref "Q2") (pin "3") (pinfunction "2_3") (pintype "passive"))
      (node (ref "R27") (pin "2") (pinfunction "2_2") (pintype "passive"))
    )
    (net (code "92") (name "Net-(IC7-XO)") (class "Default")
      (node (ref "C21") (pin "2") (pinfunction "2_2") (pintype "passive"))
      (node (ref "IC7") (pin "8") (pinfunction "XO_8") (pintype "bidirectional"))
      (node (ref "Q2") (pin "1") (pinfunction "1_1") (pintype "passive"))
      (node (ref "R27") (pin "1") (pinfunction "1_1") (pintype "passive"))
    )
    (net (code "93") (name "Net-(J1-D+)") (class "Default")
      (node (ref "J1") (pin "3") (pinfunction "D+_3") (pintype "bidirectional"))
      (node (ref "R29") (pin "2") (pinfunction "2_2") (pintype "passive"))
    )
    (net (code "94") (name "Net-(J1-D-)") (class "Default")
      (node (ref "J1") (pin "2") (pinfunction "D-_2") (pintype "bidirectional"))
      (node (ref "R28") (pin "2") (pinfunction "2_2") (pintype "passive"))
    )
    (net (code "95") (name "Net-(LED2-PadA)") (class "Default")
      (node (ref "LED2") (pin "A") (pinfunction "A_A") (pintype "passive"))
      (node (ref "R11") (pin "2") (pinfunction "2_2") (pintype "passive"))
    )
    (net (code "96") (name "Net-(LED3A-A)") (class "Default")
      (node (ref "LED3") (pin "P6") (pinfunction "A_P6") (pintype "passive"))
      (node (ref "R3") (pin "2") (pinfunction "2_2") (pintype "passive"))
    )
    (net (code "97") (name "Net-(LED3B-A)") (class "Default")
      (node (ref "LED3") (pin "P5") (pinfunction "A_P5") (pintype "passive"))
      (node (ref "R13") (pin "2") (pinfunction "2_2") (pintype "passive"))
    )
    (net (code "98") (name "Net-(LED3C-A)") (class "Default")
      (node (ref "LED3") (pin "P4") (pinfunction "A_P4") (pintype "passive"))
      (node (ref "R2") (pin "2") (pinfunction "2_2") (pintype "passive"))
    )
    (net (code "99") (name "Net-(MICRO_SD1-DAT0)") (class "Default")
      (node (ref "MICRO_SD1") (pin "7") (pinfunction "DAT0_7") (pintype "bidirectional"))
      (node (ref "R20") (pin "2") (pinfunction "2_2") (pintype "passive"))
    )
    (net (code "100") (name "Net-(Q1-2)") (class "Default")
      (node (ref "C16") (pin "2") (pinfunction "2_2") (pintype "passive"))
      (node (ref "Q1") (pin "3") (pinfunction "2_3") (pintype "passive"))
      (node (ref "R19") (pin "2") (pinfunction "2_2") (pintype "passive"))
      (node (ref "U1") (pin "33") (pinfunction "XTAL2_33") (pintype "output"))
    )
    (net (code "101") (name "Net-(U1-XTAL1)") (class "Default")
      (node (ref "C17") (pin "2") (pinfunction "2_2") (pintype "passive"))
      (node (ref "Q1") (pin "1") (pinfunction "1_1") (pintype "passive"))
      (node (ref "R19") (pin "1") (pinfunction "1_1") (pintype "passive"))
      (node (ref "U1") (pin "34") (pinfunction "XTAL1_34") (pintype "input"))
    )
    (net (code "102") (name "O0") (class "Default")
      (node (ref "IC5") (pin "9") (pinfunction "8D_9") (pintype "input"))
      (node (ref "U1") (pin "89") (pinfunction "PK0(ADC8/PCINT16)_89") (pintype "bidirectional"))
    )
    (net (code "103") (name "O1") (class "Default")
      (node (ref "IC5") (pin "8") (pinfunction "7D_8") (pintype "input"))
      (node (ref "U1") (pin "88") (pinfunction "PK1(ADC9/PCINT17)_88") (pintype "bidirectional"))
    )
    (net (code "104") (name "O2") (class "Default")
      (node (ref "IC5") (pin "7") (pinfunction "6D_7") (pintype "input"))
      (node (ref "U1") (pin "87") (pinfunction "PK2(ADC10/PCINT18)_87") (pintype "bidirectional"))
    )
    (net (code "105") (name "O3") (class "Default")
      (node (ref "IC5") (pin "6") (pinfunction "5D_6") (pintype "input"))
      (node (ref "U1") (pin "86") (pinfunction "PK3(ADC11/PCINT19)_86") (pintype "bidirectional"))
    )
    (net (code "106") (name "O4") (class "Default")
      (node (ref "IC5") (pin "5") (pinfunction "4D_5") (pintype "input"))
      (node (ref "U1") (pin "85") (pinfunction "PK4(ADC12/PCINT20)_85") (pintype "bidirectional"))
    )
    (net (code "107") (name "O5") (class "Default")
      (node (ref "IC5") (pin "4") (pinfunction "3D_4") (pintype "input"))
      (node (ref "U1") (pin "84") (pinfunction "PK5(ADC13/PCINT21)_84") (pintype "bidirectional"))
    )
    (net (code "108") (name "O6") (class "Default")
      (node (ref "IC5") (pin "3") (pinfunction "2D_3") (pintype "input"))
      (node (ref "U1") (pin "83") (pinfunction "PK6(ADC14/PCINT22)_83") (pintype "bidirectional"))
    )
    (net (code "109") (name "O7") (class "Default")
      (node (ref "IC5") (pin "2") (pinfunction "1D_2") (pintype "input"))
      (node (ref "U1") (pin "82") (pinfunction "PK7(ADC15/PCINT23)_82") (pintype "bidirectional"))
    )
    (net (code "110") (name "OE_OL") (class "Default")
      (node (ref "IC9") (pin "1") (pinfunction "OC_1") (pintype "input"))
      (node (ref "U1") (pin "13") (pinfunction "PH1(TXD2)_13") (pintype "bidirectional"))
    )
    (net (code "111") (name "PAGE_A8") (class "Default")
      (node (ref "IC4") (pin "80") (pinfunction "FB6MC11_80") (pintype "bidirectional"))
      (node (ref "U1") (pin "41") (pinfunction "PL6_41") (pintype "bidirectional"))
    )
    (net (code "112") (name "RD+") (class "Default")
      (node (ref "IC7") (pin "5") (pinfunction "D+_5") (pintype "bidirectional"))
      (node (ref "R29") (pin "1") (pinfunction "1_1") (pintype "passive"))
    )
    (net (code "113") (name "RD-") (class "Default")
      (node (ref "IC7") (pin "6") (pinfunction "D-_6") (pintype "bidirectional"))
      (node (ref "R28") (pin "1") (pinfunction "1_1") (pintype "passive"))
    )
    (net (code "114") (name "RESET") (class "Default")
      (node (ref "C5") (pin "2") (pinfunction "2_2") (pintype "passive"))
      (node (ref "C9") (pin "1") (pinfunction "1_1") (pintype "passive"))
      (node (ref "D1") (pin "A") (pinfunction "A_A") (pintype "passive"))
      (node (ref "JP6") (pin "5") (pinfunction "5_5") (pintype "passive"))
      (node (ref "R15") (pin "1") (pinfunction "1_1") (pintype "passive"))
      (node (ref "S1") (pin "2") (pinfunction "S_2") (pintype "passive"))
      (node (ref "U1") (pin "30") (pinfunction "RESET_30") (pintype "input"))
    )
    (net (code "115") (name "RIGHT") (class "Default")
      (node (ref "IC4") (pin "68") (pinfunction "FB8MC11_68") (pintype "bidirectional"))
      (node (ref "J2") (pin "4") (pinfunction "4_4") (pintype "passive"))
    )
    (net (code "116") (name "ROM_WR_EN") (class "Default")
      (node (ref "IC4") (pin "79") (pinfunction "FB6MC9_79") (pintype "bidirectional"))
      (node (ref "U1") (pin "36") (pinfunction "PL1(ICP5)_36") (pintype "bidirectional"))
    )
    (net (code "117") (name "RST_CTRL_REG") (class "Default")
      (node (ref "IC4") (pin "82") (pinfunction "FB6MC14_82") (pintype "bidirectional"))
      (node (ref "U1") (pin "26") (pinfunction "(OC0A/OC1C/PCINT7)PB7_26") (pintype "bidirectional"))
    )
    (net (code "118") (name "RST_DATA_REG") (class "Default")
      (node (ref "IC4") (pin "81") (pinfunction "FB6MC12_81") (pintype "bidirectional"))
      (node (ref "U1") (pin "63") (pinfunction "PJ0(RXD3/PCINT9)_63") (pintype "bidirectional"))
    )
    (net (code "119") (name "RX0") (class "Default")
      (node (ref "R23") (pin "1") (pinfunction "1_1") (pintype "passive"))
      (node (ref "U1") (pin "3") (pinfunction "(TXD0)PE1_3") (pintype "bidirectional"))
    )
    (net (code "120") (name "SCK_LLS") (class "Default")
      (node (ref "IC6") (pin "6") (pinfunction "O_6") (pintype "tri_state"))
      (node (ref "MICRO_SD1") (pin "5") (pinfunction "CLK_5") (pintype "bidirectional"))
    )
    (net (code "121") (name "SCLK") (class "Default")
      (node (ref "JP6") (pin "3") (pinfunction "3_3") (pintype "passive"))
      (node (ref "R18") (pin "1") (pinfunction "1_1") (pintype "passive"))
      (node (ref "U1") (pin "20") (pinfunction "(SCK/PCINT1)PB1_20") (pintype "bidirectional"))
    )
    (net (code "122") (name "SD_LED") (class "Default")
      (node (ref "LED2") (pin "C") (pinfunction "C_C") (pintype "passive"))
      (node (ref "U1") (pin "37") (pinfunction "PL2(T5)_37") (pintype "bidirectional"))
    )
    (net (code "123") (name "SEL_128CHARS") (class "Default")
      (node (ref "IC4") (pin "78") (pinfunction "FB6MC8_78") (pintype "bidirectional"))
      (node (ref "U1") (pin "35") (pinfunction "PL0(ICP4)_35") (pintype "bidirectional"))
    )
    (net (code "124") (name "SPARE1") (class "Default")
      (node (ref "IC4") (pin "77") (pinfunction "FB6MC6_77") (pintype "bidirectional"))
      (node (ref "U1") (pin "38") (pinfunction "PL3(OC5A)_38") (pintype "bidirectional"))
    )
    (net (code "125") (name "SS_SD") (class "Default")
      (node (ref "R21") (pin "1") (pinfunction "1_1") (pintype "passive"))
      (node (ref "U1") (pin "19") (pinfunction "(SS/PCINT0)PB0_19") (pintype "bidirectional"))
    )
    (net (code "126") (name "TCK") (class "Default")
      (node (ref "IC4") (pin "48") (pinfunction "TCK_48") (pintype "passive"))
      (node (ref "JP3") (pin "1") (pinfunction "1_1") (pintype "passive"))
      (node (ref "R7") (pin "2") (pinfunction "2_2") (pintype "passive"))
      (node (ref "R8") (pin "2") (pinfunction "2_2") (pintype "passive"))
    )
    (net (code "127") (name "TCK'") (class "Default")
      (node (ref "R7") (pin "1") (pinfunction "1_1") (pintype "passive"))
      (node (ref "U1") (pin "24") (pinfunction "(OC1A/PCINT5)PB5_24") (pintype "bidirectional"))
    )
    (net (code "128") (name "TDI") (class "Default")
      (node (ref "IC4") (pin "45") (pinfunction "TDI_45") (pintype "passive"))
      (node (ref "JP3") (pin "3") (pinfunction "3_3") (pintype "passive"))
      (node (ref "R5") (pin "2") (pinfunction "2_2") (pintype "passive"))
      (node (ref "R9") (pin "2") (pinfunction "2_2") (pintype "passive"))
    )
    (net (code "129") (name "TDI'") (class "Default")
      (node (ref "R5") (pin "1") (pinfunction "1_1") (pintype "passive"))
      (node (ref "U1") (pin "18") (pinfunction "PH6(OC2B)_18") (pintype "bidirectional"))
    )
    (net (code "130") (name "TDO") (class "Default")
      (node (ref "IC4") (pin "83") (pinfunction "TDO_83") (pintype "passive"))
      (node (ref "JP3") (pin "2") (pinfunction "2_2") (pintype "passive"))
      (node (ref "R6") (pin "2") (pinfunction "2_2") (pintype "passive"))
    )
    (net (code "131") (name "TDO'") (class "Default")
      (node (ref "R6") (pin "1") (pinfunction "1_1") (pintype "passive"))
      (node (ref "U1") (pin "17") (pinfunction "PH5(OC4C)_17") (pintype "bidirectional"))
    )
    (net (code "132") (name "TMS") (class "Default")
      (node (ref "IC4") (pin "47") (pinfunction "TMS_47") (pintype "passive"))
      (node (ref "JP3") (pin "4") (pinfunction "4_4") (pintype "passive"))
      (node (ref "R10") (pin "2") (pinfunction "2_2") (pintype "passive"))
      (node (ref "R4") (pin "2") (pinfunction "2_2") (pintype "passive"))
    )
    (net (code "133") (name "TMS'") (class "Default")
      (node (ref "R4") (pin "1") (pinfunction "1_1") (pintype "passive"))
      (node (ref "U1") (pin "23") (pinfunction "(OC2A/PCINT4)PB4_23") (pintype "bidirectional"))
    )
    (net (code "134") (name "TX0") (class "Default")
      (node (ref "R22") (pin "1") (pinfunction "1_1") (pintype "passive"))
      (node (ref "U1") (pin "2") (pinfunction "(RXD0/PCIN8)PE0_2") (pintype "bidirectional"))
    )
    (net (code "135") (name "UP") (class "Default")
      (node (ref "IC4") (pin "65") (pinfunction "FB8MC6_65") (pintype "bidirectional"))
      (node (ref "J2") (pin "1") (pinfunction "1_1") (pintype "passive"))
    )
    (net (code "136") (name "VCC") (class "Default")
      (node (ref "C1") (pin "1") (pinfunction "1_1") (pintype "passive"))
      (node (ref "C13") (pin "1") (pinfunction "1_1") (pintype "passive"))
      (node (ref "C14") (pin "1") (pinfunction "1_1") (pintype "passive"))
      (node (ref "C15") (pin "1") (pinfunction "1_1") (pintype "passive"))
      (node (ref "C19") (pin "1") (pinfunction "1_1") (pintype "passive"))
      (node (ref "C2") (pin "1") (pinfunction "1_1") (pintype "passive"))
      (node (ref "C3") (pin "1") (pinfunction "1_1") (pintype "passive"))
      (node (ref "D1") (pin "C") (pinfunction "C_C") (pintype "passive"))
      (node (ref "IC1") (pin "2") (pinfunction "VO_2") (pintype "passive"))
      (node (ref "IC2") (pin "3") (pinfunction "VIN_3") (pintype "input"))
      (node (ref "IC3") (pin "12") (pinfunction "I_12") (pintype "input"))
      (node (ref "IC3") (pin "13") (pinfunction "OE_13") (pintype "input"))
      (node (ref "IC3") (pin "2") (pinfunction "I_2") (pintype "input"))
      (node (ref "IC3") (pin "5") (pinfunction "I_5") (pintype "input"))
      (node (ref "IC7") (pin "16") (pinfunction "VCC_16") (pintype "bidirectional"))
      (node (ref "J1") (pin "1") (pinfunction "VBUS_1") (pintype "power_in"))
      (node (ref "JP6") (pin "2") (pinfunction "2_2") (pintype "passive"))
      (node (ref "R11") (pin "1") (pinfunction "1_1") (pintype "passive"))
      (node (ref "R15") (pin "2") (pinfunction "2_2") (pintype "passive"))
      (node (ref "SJ1") (pin "2") (pinfunction "2_2") (pintype "passive"))
      (node (ref "U1") (pin "10") (pinfunction "VCC_10") (pintype "power_in"))
      (node (ref "U1") (pin "100") (pinfunction "AVCC_100") (pintype "power_in"))
      (node (ref "U1") (pin "31") (pinfunction "VCC1_31") (pintype "power_in"))
      (node (ref "U1") (pin "61") (pinfunction "VCC2_61") (pintype "power_in"))
      (node (ref "U1") (pin "80") (pinfunction "VCC3_80") (pintype "power_in"))
      (node (ref "U2") (pin "32") (pinfunction "VCC_32") (pintype "power_in"))
    )
    (net (code "137") (name "unconnected-(IC3D-O-Pad11)") (class "Default")
      (node (ref "IC3") (pin "11") (pinfunction "O_11") (pintype "tri_state"))
    )
    (net (code "138") (name "unconnected-(IC7-CTS-Pad9)") (class "Default")
      (node (ref "IC7") (pin "9") (pinfunction "CTS_9") (pintype "bidirectional"))
    )
    (net (code "139") (name "unconnected-(IC7-DCD-Pad12)") (class "Default")
      (node (ref "IC7") (pin "12") (pinfunction "DCD_12") (pintype "bidirectional"))
    )
    (net (code "140") (name "unconnected-(IC7-DSR-Pad10)") (class "Default")
      (node (ref "IC7") (pin "10") (pinfunction "DSR_10") (pintype "bidirectional"))
    )
    (net (code "141") (name "unconnected-(IC7-RI-Pad11)") (class "Default")
      (node (ref "IC7") (pin "11") (pinfunction "RI_11") (pintype "bidirectional"))
    )
    (net (code "142") (name "unconnected-(IC7-RS232-Pad15)") (class "Default")
      (node (ref "IC7") (pin "15") (pinfunction "RS232_15") (pintype "bidirectional"))
    )
    (net (code "143") (name "unconnected-(IC7-RTS-Pad14)") (class "Default")
      (node (ref "IC7") (pin "14") (pinfunction "RTS_14") (pintype "bidirectional"))
    )
    (net (code "144") (name "unconnected-(J1-ID-Pad4)") (class "Default")
      (node (ref "J1") (pin "4") (pinfunction "ID_4") (pintype "bidirectional"))
    )
    (net (code "145") (name "unconnected-(J2-Pad5)") (class "Default")
      (node (ref "J2") (pin "5") (pinfunction "5_5") (pintype "passive"))
    )
    (net (code "146") (name "unconnected-(J2-Pad7)") (class "Default")
      (node (ref "J2") (pin "7") (pinfunction "7_7") (pintype "passive"))
    )
    (net (code "147") (name "unconnected-(J2-Pad9)") (class "Default")
      (node (ref "J2") (pin "9") (pinfunction "9_9") (pintype "passive"))
    )
    (net (code "148") (name "unconnected-(MICRO_SD1-CD-PadCD1)") (class "Default")
      (node (ref "MICRO_SD1") (pin "CD1") (pinfunction "CD_CD1") (pintype "passive"))
    )
    (net (code "149") (name "unconnected-(MICRO_SD1-DAT1-Pad8)") (class "Default")
      (node (ref "MICRO_SD1") (pin "8") (pinfunction "DAT1_8") (pintype "bidirectional"))
    )
    (net (code "150") (name "unconnected-(MICRO_SD1-DAT2-Pad1)") (class "Default")
      (node (ref "MICRO_SD1") (pin "1") (pinfunction "DAT2_1") (pintype "bidirectional"))
    )
    (net (code "151") (name "unconnected-(U1-(CLKO{slash}ICP3{slash}INT7)PE7-Pad9)") (class "Default")
      (node (ref "U1") (pin "9") (pinfunction "(CLKO/ICP3/INT7)PE7_9") (pintype "bidirectional"))
    )
    (net (code "152") (name "unconnected-(U1-(ICP1)PD4-Pad47)") (class "Default")
      (node (ref "U1") (pin "47") (pinfunction "(ICP1)PD4_47") (pintype "bidirectional"))
    )
    (net (code "153") (name "unconnected-(U1-(T1)PD6-Pad49)") (class "Default")
      (node (ref "U1") (pin "49") (pinfunction "(T1)PD6_49") (pintype "bidirectional"))
    )
    (net (code "154") (name "unconnected-(U1-(T3{slash}INT6)PE6-Pad8)") (class "Default")
      (node (ref "U1") (pin "8") (pinfunction "(T3/INT6)PE6_8") (pintype "bidirectional"))
    )
    (net (code "155") (name "unconnected-(U1-(TOSC1)PG4-Pad29)") (class "Default")
      (node (ref "U1") (pin "29") (pinfunction "(TOSC1)PG4_29") (pintype "bidirectional"))
    )
    (net (code "156") (name "unconnected-(U1-(TOSC2)PG3-Pad28)") (class "Default")
      (node (ref "U1") (pin "28") (pinfunction "(TOSC2)PG3_28") (pintype "bidirectional"))
    )
    (net (code "157") (name "unconnected-(U1-(XCK0{slash}AIN0)PE2-Pad4)") (class "Default")
      (node (ref "U1") (pin "4") (pinfunction "(XCK0/AIN0)PE2_4") (pintype "bidirectional"))
    )
    (net (code "158") (name "unconnected-(U1-(XCK1)PD5-Pad48)") (class "Default")
      (node (ref "U1") (pin "48") (pinfunction "(XCK1)PD5_48") (pintype "bidirectional"))
    )
    (net (code "159") (name "unconnected-(U1-PH2(XCK2)-Pad14)") (class "Default")
      (node (ref "U1") (pin "14") (pinfunction "PH2(XCK2)_14") (pintype "bidirectional"))
    )
    (net (code "160") (name "unconnected-(U1-PH7(T4)-Pad27)") (class "Default")
      (node (ref "U1") (pin "27") (pinfunction "PH7(T4)_27") (pintype "bidirectional"))
    )
    (net (code "161") (name "unconnected-(U1-PJ2(XCK3{slash}PCINT11)-Pad65)") (class "Default")
      (node (ref "U1") (pin "65") (pinfunction "PJ2(XCK3/PCINT11)_65") (pintype "bidirectional"))
    )
    (net (code "162") (name "unconnected-(U1-PJ3(PCINT12)-Pad66)") (class "Default")
      (node (ref "U1") (pin "66") (pinfunction "PJ3(PCINT12)_66") (pintype "bidirectional"))
    )
    (net (code "163") (name "unconnected-(U1-PJ4(PCINT13)-Pad67)") (class "Default")
      (node (ref "U1") (pin "67") (pinfunction "PJ4(PCINT13)_67") (pintype "bidirectional"))
    )
    (net (code "164") (name "{slash}BUSAK") (class "Default")
      (node (ref "18A") (pin "1") (pinfunction "P_1") (pintype "passive"))
    )
    (net (code "165") (name "{slash}BUSRQ") (class "Default")
      (node (ref "20A") (pin "1") (pinfunction "P_1") (pintype "passive"))
    )
    (net (code "166") (name "{slash}CLOCK") (class "Default")
      (node (ref "6B") (pin "1") (pinfunction "P_1") (pintype "passive"))
      (node (ref "IC4") (pin "22") (pinfunction "GCK1_22") (pintype "bidirectional"))
    )
    (net (code "167") (name "{slash}HALT") (class "Default")
      (node (ref "13A") (pin "1") (pinfunction "P_1") (pintype "passive"))
      (node (ref "SJ2") (pin "2") (pinfunction "2_2") (pintype "passive"))
    )
    (net (code "168") (name "{slash}IORQ") (class "Default")
      (node (ref "15A") (pin "1") (pinfunction "P_1") (pintype "passive"))
      (node (ref "IC4") (pin "43") (pinfunction "FB5MC14_43") (pintype "bidirectional"))
    )
    (net (code "169") (name "{slash}M1") (class "Default")
      (node (ref "22A") (pin "1") (pinfunction "P_1") (pintype "passive"))
      (node (ref "IC4") (pin "61") (pinfunction "FB7MC17_61") (pintype "bidirectional"))
    )
    (net (code "170") (name "{slash}MEM_CE") (class "Default")
      (node (ref "IC4") (pin "97") (pinfunction "FB4MC17_97") (pintype "bidirectional"))
      (node (ref "U1") (pin "50") (pinfunction "(T0)PD7_50") (pintype "bidirectional"))
      (node (ref "U2") (pin "22") (pinfunction "CE_22") (pintype "input"))
    )
    (net (code "171") (name "{slash}MEM_OE") (class "Default")
      (node (ref "IC4") (pin "12") (pinfunction "FB1MC3_12") (pintype "bidirectional"))
      (node (ref "U1") (pin "52") (pinfunction "(RD)PG1_52") (pintype "bidirectional"))
      (node (ref "U2") (pin "24") (pinfunction "OE_24") (pintype "input"))
    )
    (net (code "172") (name "{slash}MREQ") (class "Default")
      (node (ref "14A") (pin "1") (pinfunction "P_1") (pintype "passive"))
      (node (ref "IC4") (pin "41") (pinfunction "FB5MC11_41") (pintype "bidirectional"))
    )
    (net (code "173") (name "{slash}NMI") (class "Default")
      (node (ref "12A") (pin "1") (pinfunction "P_1") (pintype "passive"))
      (node (ref "IC4") (pin "36") (pinfunction "FB5MC5_36") (pintype "bidirectional"))
    )
    (net (code "174") (name "{slash}OE_CTRL_CLOCK") (class "Default")
      (node (ref "IC3") (pin "10") (pinfunction "OE_10") (pintype "input"))
      (node (ref "IC4") (pin "10") (pinfunction "FB2MC17_10") (pintype "bidirectional"))
    )
    (net (code "175") (name "{slash}OE_IL") (class "Default")
      (node (ref "IC4") (pin "15") (pinfunction "FB1MC8_15") (pintype "bidirectional"))
      (node (ref "IC5") (pin "1") (pinfunction "OC_1") (pintype "input"))
    )
    (net (code "176") (name "{slash}OE_RAMCS") (class "Default")
      (node (ref "IC3") (pin "4") (pinfunction "OE_4") (pintype "input"))
      (node (ref "IC4") (pin "17") (pinfunction "FB1MC11_17") (pintype "bidirectional"))
    )
    (net (code "177") (name "{slash}OE_ROMCS") (class "Default")
      (node (ref "IC3") (pin "1") (pinfunction "OE_1") (pintype "input"))
      (node (ref "IC4") (pin "14") (pinfunction "FB1MC6_14") (pintype "bidirectional"))
    )
    (net (code "178") (name "{slash}RAMCS") (class "Default")
      (node (ref "2A") (pin "1") (pinfunction "P_1") (pintype "passive"))
      (node (ref "IC3") (pin "6") (pinfunction "O_6") (pintype "tri_state"))
    )
    (net (code "179") (name "{slash}RD") (class "Default")
      (node (ref "16A") (pin "1") (pinfunction "P_1") (pintype "passive"))
      (node (ref "IC4") (pin "49") (pinfunction "FB5MC17_49") (pintype "bidirectional"))
    )
    (net (code "180") (name "{slash}RESET") (class "Default")
      (node (ref "21A") (pin "1") (pinfunction "P_1") (pintype "passive"))
      (node (ref "IC4") (pin "71") (pinfunction "FB8MC14_71") (pintype "bidirectional"))
      (node (ref "U1") (pin "15") (pinfunction "PH3(OC4A)_15") (pintype "bidirectional"))
    )
    (net (code "181") (name "{slash}RFSH") (class "Default")
      (node (ref "23A") (pin "1") (pinfunction "P_1") (pintype "passive"))
      (node (ref "IC4") (pin "64") (pinfunction "FB8MC5_64") (pintype "bidirectional"))
    )
    (net (code "182") (name "{slash}ROMCS") (class "Default")
      (node (ref "23B") (pin "1") (pinfunction "P_1") (pintype "passive"))
      (node (ref "IC3") (pin "3") (pinfunction "O_3") (pintype "tri_state"))
    )
    (net (code "183") (name "{slash}WAIT") (class "Default")
      (node (ref "19A") (pin "1") (pinfunction "P_1") (pintype "passive"))
      (node (ref "IC4") (pin "56") (pinfunction "FB7MC11_56") (pintype "bidirectional"))
      (node (ref "U1") (pin "42") (pinfunction "PL7_42") (pintype "bidirectional"))
    )
    (net (code "184") (name "{slash}WR") (class "Default")
      (node (ref "17A") (pin "1") (pinfunction "P_1") (pintype "passive"))
      (node (ref "IC4") (pin "52") (pinfunction "FB7MC5_52") (pintype "bidirectional"))
    )
    (net (code "185") (name "{slash}WR'") (class "Default")
      (node (ref "IC4") (pin "13") (pinfunction "FB1MC5_13") (pintype "bidirectional"))
      (node (ref "U1") (pin "51") (pinfunction "(WR)PG0_51") (pintype "bidirectional"))
      (node (ref "U2") (pin "29") (pinfunction "WE_29") (pintype "input"))
    )
  )
)
